# 1206_1210.net
KiCad netlist of a schematic drawn in EAGLE
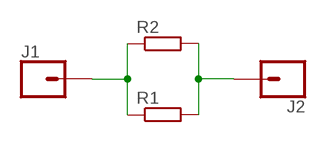
[diagram p0: schematic, sheet 1]

(export (version "E")
  (design (tool "Eeschema 10.0.6"))
  (components
    (comp (ref "J1")
      (value "CONN_01")
      (footprint "eagle-import:1X01")
      (libsource (lib "eagle-import") (part "CONN_01"))
    )
    (comp (ref "J2")
      (value "CONN_01")
      (footprint "eagle-import:1X01")
      (libsource (lib "eagle-import") (part "CONN_01"))
    )
    (comp (ref "R1")
      (value "R-EU_R1210")
      (footprint "eagle-import:R1210")
      (libsource (lib "eagle-import") (part "R-EU_R1210"))
    )
    (comp (ref "R2")
      (value "R-EU_R1206")
      (footprint "eagle-import:R1206")
      (libsource (lib "eagle-import") (part "R-EU_R1206"))
    )
  )
  (nets
    (net (code "1") (name "Net-(J1-Pad1)") (class "Default")
      (node (ref "J1") (pin "1") (pinfunction "1_1") (pintype "passive"))
      (node (ref "R1") (pin "1") (pinfunction "1_1") (pintype "passive"))
      (node (ref "R2") (pin "1") (pinfunction "1_1") (pintype "passive"))
    )
    (net (code "2") (name "Net-(J2-Pad1)") (class "Default")
      (node (ref "J2") (pin "1") (pinfunction "1_1") (pintype "passive"))
      (node (ref "R1") (pin "2") (pinfunction "2_2") (pintype "passive"))
      (node (ref "R2") (pin "2") (pinfunction "2_2") (pintype "passive"))
    )
  )
)
